# fever_meter_v2.net
KiCad netlist of a schematic drawn in EAGLE
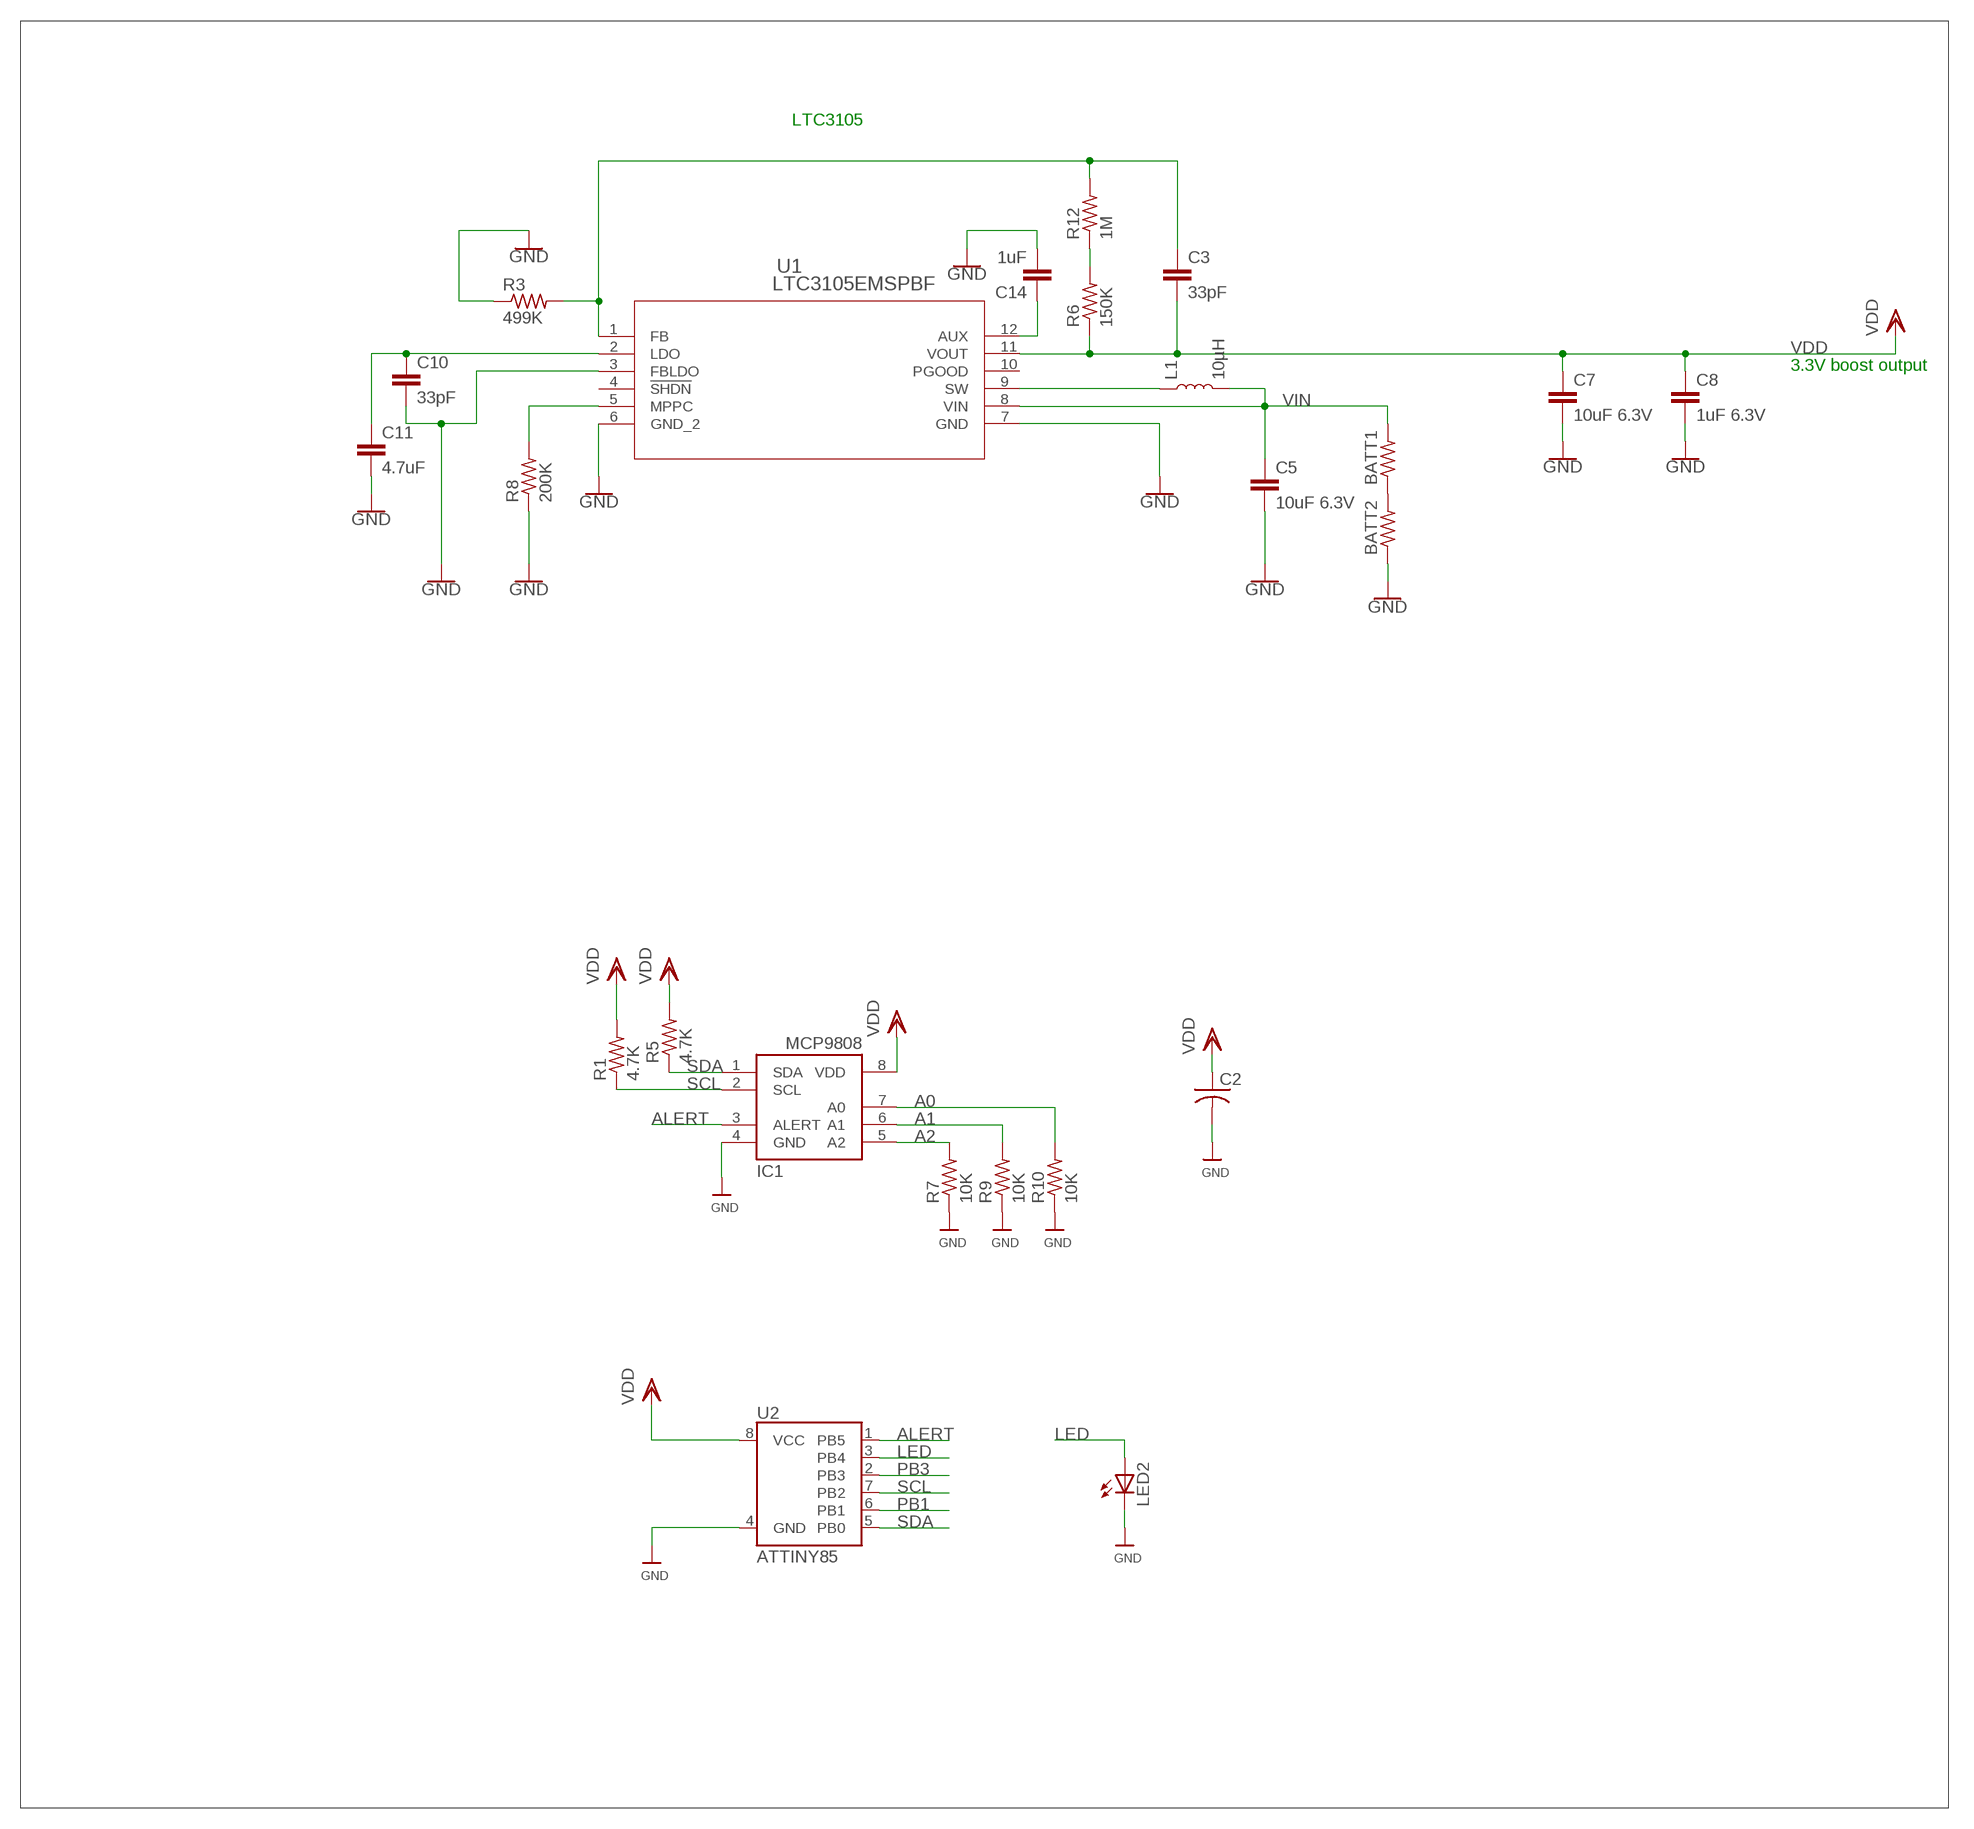
[diagram p0: schematic, sheet 1]

(export (version "E")
  (design (tool "Eeschema 10.0.6"))
  (components
    (comp (ref "BATT1")
      (value "R-US_M0805")
      (footprint "eagle-import:M0805")
      (libsource (lib "eagle-import") (part "adafruit_420_R-US_M0805"))
    )
    (comp (ref "BATT2")
      (value "R-US_M0805")
      (footprint "eagle-import:M0805")
      (libsource (lib "eagle-import") (part "adafruit_420_R-US_M0805"))
    )
    (comp (ref "C2")
      (value "C-USC1206")
      (footprint "eagle-import:C1206")
      (libsource (lib "eagle-import") (part "C-USC1206"))
    )
    (comp (ref "C3")
      (value "33pF")
      (footprint "eagle-import:1206")
      (libsource (lib "eagle-import") (part "2.2UF-1206-50V-10%"))
    )
    (comp (ref "C5")
      (value "10uF 6.3V")
      (footprint "eagle-import:1206")
      (libsource (lib "eagle-import") (part "2.2UF-1206-50V-10%"))
    )
    (comp (ref "C7")
      (value "10uF 6.3V")
      (footprint "eagle-import:1206")
      (libsource (lib "eagle-import") (part "2.2UF-1206-50V-10%"))
    )
    (comp (ref "C8")
      (value "1uF 6.3V")
      (footprint "eagle-import:1206")
      (libsource (lib "eagle-import") (part "2.2UF-1206-50V-10%"))
    )
    (comp (ref "C10")
      (value "33pF")
      (footprint "eagle-import:1206")
      (libsource (lib "eagle-import") (part "2.2UF-1206-50V-10%"))
    )
    (comp (ref "C11")
      (value "4.7uF")
      (footprint "eagle-import:1206")
      (libsource (lib "eagle-import") (part "2.2UF-1206-50V-10%"))
    )
    (comp (ref "C14")
      (value "1uF")
      (footprint "eagle-import:1206")
      (libsource (lib "eagle-import") (part "2.2UF-1206-50V-10%"))
    )
    (comp (ref "IC1")
      (value "MCP9808-E/MS")
      (footprint "eagle-import:MSOP8_0.65MM")
      (libsource (lib "eagle-import") (part "MCP9808-E/MS"))
    )
    (comp (ref "L1")
      (value "10µH")
      (footprint "eagle-import:INDUCTOR_2.2UH")
      (libsource (lib "eagle-import") (part "INDUCTOR-VLF4012AT-2.2UH"))
    )
    (comp (ref "LED2")
      (value "LEDSMT1206")
      (footprint "eagle-import:1206")
      (libsource (lib "eagle-import") (part "LEDSMT1206"))
    )
    (comp (ref "R1")
      (value "4.7K")
      (footprint "eagle-import:M1206")
      (libsource (lib "eagle-import") (part "R-US_M1206"))
    )
    (comp (ref "R3")
      (value "499K")
      (footprint "eagle-import:R1206")
      (libsource (lib "eagle-import") (part "R-US_R1206"))
    )
    (comp (ref "R5")
      (value "4.7K")
      (footprint "eagle-import:M1206")
      (libsource (lib "eagle-import") (part "R-US_M1206"))
    )
    (comp (ref "R6")
      (value "150K")
      (footprint "eagle-import:R1206")
      (libsource (lib "eagle-import") (part "R-US_R1206"))
    )
    (comp (ref "R7")
      (value "10K")
      (footprint "eagle-import:M1206")
      (libsource (lib "eagle-import") (part "R-US_M1206"))
    )
    (comp (ref "R8")
      (value "200K")
      (footprint "eagle-import:R1206")
      (libsource (lib "eagle-import") (part "R-US_R1206"))
    )
    (comp (ref "R9")
      (value "10K")
      (footprint "eagle-import:M1206")
      (libsource (lib "eagle-import") (part "R-US_M1206"))
    )
    (comp (ref "R10")
      (value "10K")
      (footprint "eagle-import:M1206")
      (libsource (lib "eagle-import") (part "R-US_M1206"))
    )
    (comp (ref "R12")
      (value "1M")
      (footprint "eagle-import:R1206")
      (libsource (lib "eagle-import") (part "R-US_R1206"))
    )
    (comp (ref "U1")
      (value "LTC3105EMSPBF")
      (footprint "eagle-import:MSOP-12_MS")
      (fields (field (name "MANUFACTURER_PART_NUMBER") "ltc3105ems#pbf"))
      (libsource (lib "eagle-import") (part "LTC3105EMSPBF"))
    )
    (comp (ref "U2")
      (value "ATTINY85")
      (footprint "eagle-import:ATTINY85")
      (libsource (lib "eagle-import") (part "ATTINY85"))
    )
  )
  (nets
    (net (code "1") (name "/A0") (class "Default")
      (node (ref "IC1") (pin "7") (pinfunction "A0_7") (pintype "input"))
      (node (ref "R10") (pin "2") (pinfunction "2_2") (pintype "passive"))
    )
    (net (code "2") (name "/A1") (class "Default")
      (node (ref "IC1") (pin "6") (pinfunction "A1_6") (pintype "input"))
      (node (ref "R9") (pin "2") (pinfunction "2_2") (pintype "passive"))
    )
    (net (code "3") (name "/A2") (class "Default")
      (node (ref "IC1") (pin "5") (pinfunction "A2_5") (pintype "input"))
      (node (ref "R7") (pin "2") (pinfunction "2_2") (pintype "passive"))
    )
    (net (code "4") (name "/ALERT") (class "Default")
      (node (ref "IC1") (pin "3") (pinfunction "ALERT_3") (pintype "open_collector"))
      (node (ref "U2") (pin "1") (pinfunction "PB5_1") (pintype "bidirectional"))
    )
    (net (code "5") (name "/LED") (class "Default")
      (node (ref "LED2") (pin "A") (pinfunction "A_A") (pintype "passive"))
      (node (ref "U2") (pin "3") (pinfunction "PB4_3") (pintype "bidirectional"))
    )
    (net (code "6") (name "/PB1") (class "Default")
      (node (ref "U2") (pin "6") (pinfunction "PB1_6") (pintype "bidirectional"))
    )
    (net (code "7") (name "/PB3") (class "Default")
      (node (ref "U2") (pin "2") (pinfunction "PB3_2") (pintype "bidirectional"))
    )
    (net (code "8") (name "/SCL") (class "Default")
      (node (ref "IC1") (pin "2") (pinfunction "SCL_2") (pintype "bidirectional"))
      (node (ref "R1") (pin "1") (pinfunction "1_1") (pintype "passive"))
      (node (ref "U2") (pin "7") (pinfunction "PB2_7") (pintype "bidirectional"))
    )
    (net (code "9") (name "/SDA") (class "Default")
      (node (ref "IC1") (pin "1") (pinfunction "SDA_1") (pintype "bidirectional"))
      (node (ref "R5") (pin "1") (pinfunction "1_1") (pintype "passive"))
      (node (ref "U2") (pin "5") (pinfunction "PB0_5") (pintype "bidirectional"))
    )
    (net (code "10") (name "/VIN") (class "Default")
      (node (ref "BATT1") (pin "2") (pinfunction "2_2") (pintype "passive"))
      (node (ref "C5") (pin "1") (pinfunction "1_1") (pintype "passive"))
      (node (ref "L1") (pin "P$2") (pinfunction "2_P$2") (pintype "passive"))
      (node (ref "U1") (pin "8") (pinfunction "VIN_8") (pintype "input"))
    )
    (net (code "11") (name "GND") (class "Default")
      (node (ref "BATT2") (pin "1") (pinfunction "1_1") (pintype "passive"))
      (node (ref "C10") (pin "2") (pinfunction "2_2") (pintype "passive"))
      (node (ref "C11") (pin "2") (pinfunction "2_2") (pintype "passive"))
      (node (ref "C14") (pin "2") (pinfunction "2_2") (pintype "passive"))
      (node (ref "C2") (pin "2") (pinfunction "2_2") (pintype "passive"))
      (node (ref "C5") (pin "2") (pinfunction "2_2") (pintype "passive"))
      (node (ref "C7") (pin "2") (pinfunction "2_2") (pintype "passive"))
      (node (ref "C8") (pin "2") (pinfunction "2_2") (pintype "passive"))
      (node (ref "IC1") (pin "4") (pinfunction "GND_4") (pintype "power_in"))
      (node (ref "LED2") (pin "C") (pinfunction "C_C") (pintype "passive"))
      (node (ref "R10") (pin "1") (pinfunction "1_1") (pintype "passive"))
      (node (ref "R3") (pin "1") (pinfunction "1_1") (pintype "passive"))
      (node (ref "R7") (pin "1") (pinfunction "1_1") (pintype "passive"))
      (node (ref "R8") (pin "1") (pinfunction "1_1") (pintype "passive"))
      (node (ref "R9") (pin "1") (pinfunction "1_1") (pintype "passive"))
      (node (ref "U1") (pin "3") (pinfunction "FBLDO_3") (pintype "bidirectional"))
      (node (ref "U1") (pin "6") (pinfunction "GND_2_6") (pintype "power_in"))
      (node (ref "U1") (pin "7") (pinfunction "GND_7") (pintype "power_in"))
      (node (ref "U2") (pin "4") (pinfunction "GND_4") (pintype "bidirectional"))
    )
    (net (code "12") (name "Net-(BATT1-Pad1)") (class "Default")
      (node (ref "BATT1") (pin "1") (pinfunction "1_1") (pintype "passive"))
      (node (ref "BATT2") (pin "2") (pinfunction "2_2") (pintype "passive"))
    )
    (net (code "13") (name "Net-(L1-1)") (class "Default")
      (node (ref "L1") (pin "P$1") (pinfunction "1_P$1") (pintype "passive"))
      (node (ref "U1") (pin "9") (pinfunction "SW_9") (pintype "passive"))
    )
    (net (code "14") (name "Net-(R12-Pad1)") (class "Default")
      (node (ref "R12") (pin "1") (pinfunction "1_1") (pintype "passive"))
      (node (ref "R6") (pin "2") (pinfunction "2_2") (pintype "passive"))
    )
    (net (code "15") (name "Net-(U1-AUX)") (class "Default")
      (node (ref "C14") (pin "1") (pinfunction "1_1") (pintype "passive"))
      (node (ref "U1") (pin "12") (pinfunction "AUX_12") (pintype "passive"))
    )
    (net (code "16") (name "Net-(U1-FB)") (class "Default")
      (node (ref "C3") (pin "1") (pinfunction "1_1") (pintype "passive"))
      (node (ref "R12") (pin "2") (pinfunction "2_2") (pintype "passive"))
      (node (ref "R3") (pin "2") (pinfunction "2_2") (pintype "passive"))
      (node (ref "U1") (pin "1") (pinfunction "FB_1") (pintype "bidirectional"))
    )
    (net (code "17") (name "Net-(U1-LDO)") (class "Default")
      (node (ref "C10") (pin "1") (pinfunction "1_1") (pintype "passive"))
      (node (ref "C11") (pin "1") (pinfunction "1_1") (pintype "passive"))
      (node (ref "U1") (pin "2") (pinfunction "LDO_2") (pintype "passive"))
    )
    (net (code "18") (name "Net-(U1-MPPC)") (class "Default")
      (node (ref "R8") (pin "2") (pinfunction "2_2") (pintype "passive"))
      (node (ref "U1") (pin "5") (pinfunction "MPPC_5") (pintype "input"))
    )
    (net (code "19") (name "VDD") (class "Default")
      (node (ref "C2") (pin "1") (pinfunction "1_1") (pintype "passive"))
      (node (ref "C3") (pin "2") (pinfunction "2_2") (pintype "passive"))
      (node (ref "C7") (pin "1") (pinfunction "1_1") (pintype "passive"))
      (node (ref "C8") (pin "1") (pinfunction "1_1") (pintype "passive"))
      (node (ref "IC1") (pin "8") (pinfunction "VDD_8") (pintype "power_in"))
      (node (ref "R1") (pin "2") (pinfunction "2_2") (pintype "passive"))
      (node (ref "R5") (pin "2") (pinfunction "2_2") (pintype "passive"))
      (node (ref "R6") (pin "1") (pinfunction "1_1") (pintype "passive"))
      (node (ref "U1") (pin "11") (pinfunction "VOUT_11") (pintype "passive"))
      (node (ref "U2") (pin "8") (pinfunction "VCC_8") (pintype "bidirectional"))
    )
    (net (code "20") (name "unconnected-(U1-PGOOD-Pad10)") (class "Default")
      (node (ref "U1") (pin "10") (pinfunction "PGOOD_10") (pintype "passive"))
    )
    (net (code "21") (name "unconnected-(U1-~{SHDN}-Pad4)") (class "Default")
      (node (ref "U1") (pin "4") (pinfunction "~{SHDN}_4") (pintype "input"))
    )
  )
)
